# ir_array.net
KiCad netlist of a schematic drawn in EAGLE
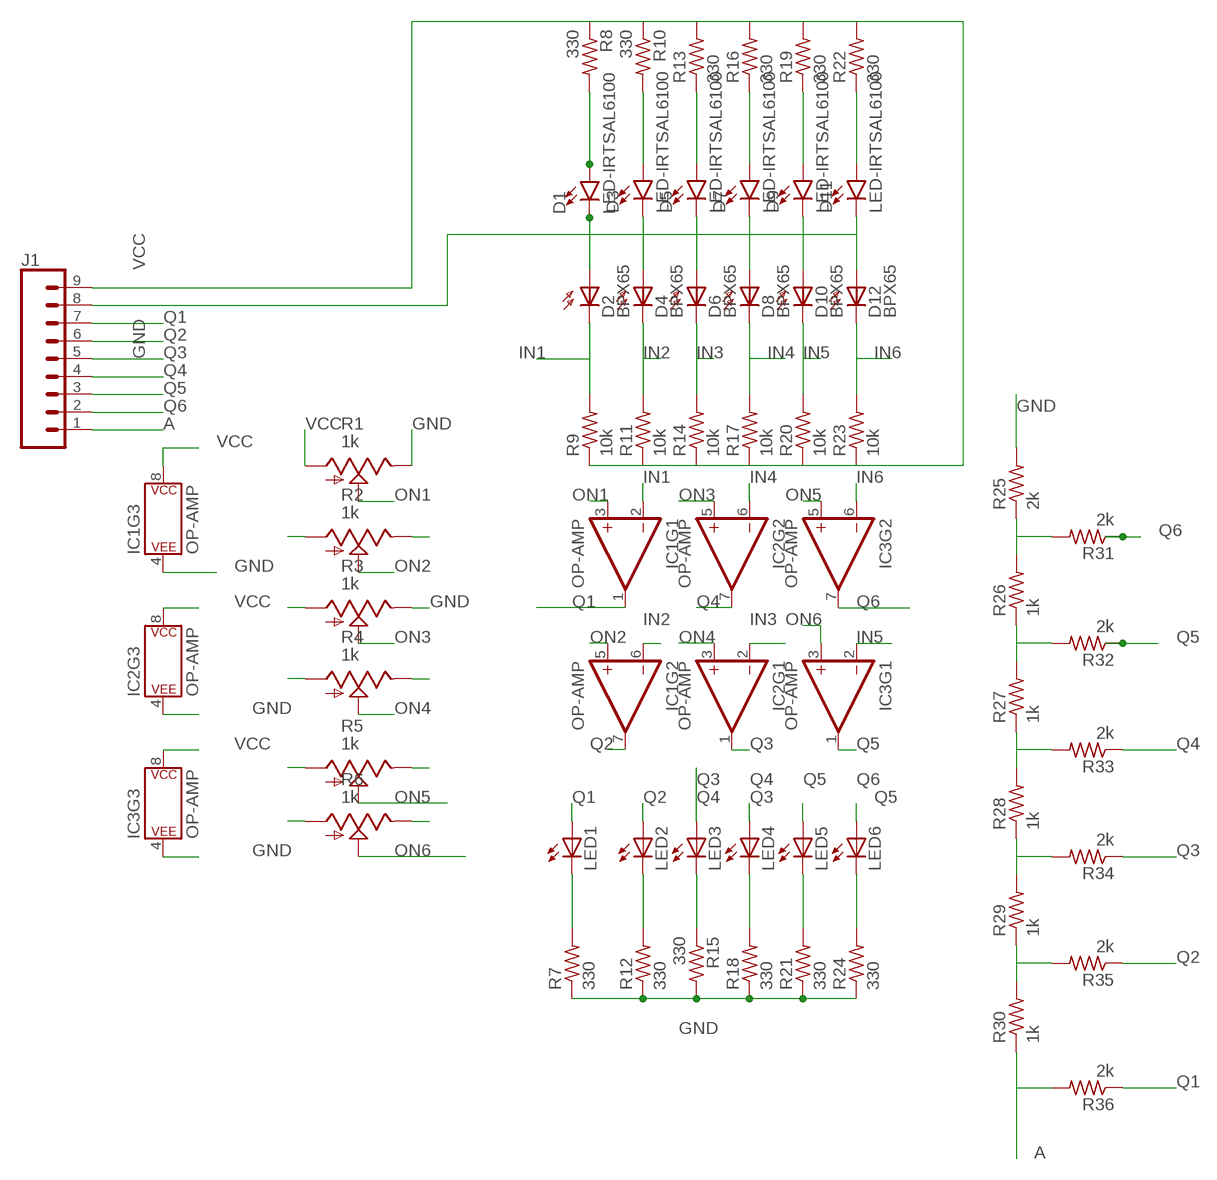
[diagram p0: schematic, sheet 1]

(export (version "E")
  (design (tool "Eeschema 10.0.6"))
  (components
    (comp (ref "D1")
      (value "LED-IRTSAL6100")
      (footprint "eagle-import:LED_5MM")
      (libsource (lib "eagle-import") (part "LED-IRTSAL6100"))
    )
    (comp (ref "D2")
      (value "BPX65")
      (footprint "eagle-import:BPX65")
      (fields (field (name "MPN") "BPX65."))
      (libsource (lib "eagle-import") (part "BPX65"))
    )
    (comp (ref "D3")
      (value "LED-IRTSAL6100")
      (footprint "eagle-import:LED_5MM")
      (libsource (lib "eagle-import") (part "LED-IRTSAL6100"))
    )
    (comp (ref "D4")
      (value "BPX65")
      (footprint "eagle-import:BPX65")
      (fields (field (name "MPN") "BPX65."))
      (libsource (lib "eagle-import") (part "BPX65"))
    )
    (comp (ref "D5")
      (value "LED-IRTSAL6100")
      (footprint "eagle-import:LED_5MM")
      (libsource (lib "eagle-import") (part "LED-IRTSAL6100"))
    )
    (comp (ref "D6")
      (value "BPX65")
      (footprint "eagle-import:BPX65")
      (fields (field (name "MPN") "BPX65."))
      (libsource (lib "eagle-import") (part "BPX65"))
    )
    (comp (ref "D7")
      (value "LED-IRTSAL6100")
      (footprint "eagle-import:LED_5MM")
      (libsource (lib "eagle-import") (part "LED-IRTSAL6100"))
    )
    (comp (ref "D8")
      (value "BPX65")
      (footprint "eagle-import:BPX65")
      (fields (field (name "MPN") "BPX65."))
      (libsource (lib "eagle-import") (part "BPX65"))
    )
    (comp (ref "D9")
      (value "LED-IRTSAL6100")
      (footprint "eagle-import:LED_5MM")
      (libsource (lib "eagle-import") (part "LED-IRTSAL6100"))
    )
    (comp (ref "D10")
      (value "BPX65")
      (footprint "eagle-import:BPX65")
      (fields (field (name "MPN") "BPX65."))
      (libsource (lib "eagle-import") (part "BPX65"))
    )
    (comp (ref "D11")
      (value "LED-IRTSAL6100")
      (footprint "eagle-import:LED_5MM")
      (libsource (lib "eagle-import") (part "LED-IRTSAL6100"))
    )
    (comp (ref "D12")
      (value "BPX65")
      (footprint "eagle-import:BPX65")
      (fields (field (name "MPN") "BPX65."))
      (libsource (lib "eagle-import") (part "BPX65"))
    )
    (comp (ref "IC1")
      (value "OP-AMP")
      (footprint "eagle-import:DIP08")
      (libsource (lib "eagle-import") (part "OPAMP-DUALDIP"))
    )
    (comp (ref "IC2")
      (value "OP-AMP")
      (footprint "eagle-import:DIP08")
      (libsource (lib "eagle-import") (part "OPAMP-DUALDIP"))
    )
    (comp (ref "IC3")
      (value "OP-AMP")
      (footprint "eagle-import:DIP08")
      (libsource (lib "eagle-import") (part "OPAMP-DUALDIP"))
    )
    (comp (ref "J1")
      (value "CONN_09")
      (footprint "eagle-import:1X09")
      (libsource (lib "eagle-import") (part "CONN_09"))
    )
    (comp (ref "LED1")
      (value "LED3MM")
      (footprint "eagle-import:LED3MM")
      (libsource (lib "eagle-import") (part "LED3MM"))
    )
    (comp (ref "LED2")
      (value "LED3MM")
      (footprint "eagle-import:LED3MM")
      (libsource (lib "eagle-import") (part "LED3MM"))
    )
    (comp (ref "LED3")
      (value "LED3MM")
      (footprint "eagle-import:LED3MM")
      (libsource (lib "eagle-import") (part "LED3MM"))
    )
    (comp (ref "LED4")
      (value "LED3MM")
      (footprint "eagle-import:LED3MM")
      (libsource (lib "eagle-import") (part "LED3MM"))
    )
    (comp (ref "LED5")
      (value "LED3MM")
      (footprint "eagle-import:LED3MM")
      (libsource (lib "eagle-import") (part "LED3MM"))
    )
    (comp (ref "LED6")
      (value "LED3MM")
      (footprint "eagle-import:LED3MM")
      (libsource (lib "eagle-import") (part "LED3MM"))
    )
    (comp (ref "R1")
      (value "1k")
      (footprint "eagle-import:B25P")
      (libsource (lib "eagle-import") (part "TRIM_US-B25P"))
    )
    (comp (ref "R2")
      (value "1k")
      (footprint "eagle-import:B25P")
      (libsource (lib "eagle-import") (part "TRIM_US-B25P"))
    )
    (comp (ref "R3")
      (value "1k")
      (footprint "eagle-import:B25P")
      (libsource (lib "eagle-import") (part "TRIM_US-B25P"))
    )
    (comp (ref "R4")
      (value "1k")
      (footprint "eagle-import:B25P")
      (libsource (lib "eagle-import") (part "TRIM_US-B25P"))
    )
    (comp (ref "R5")
      (value "1k")
      (footprint "eagle-import:B25P")
      (libsource (lib "eagle-import") (part "TRIM_US-B25P"))
    )
    (comp (ref "R6")
      (value "1k")
      (footprint "eagle-import:B25P")
      (libsource (lib "eagle-import") (part "TRIM_US-B25P"))
    )
    (comp (ref "R7")
      (value "330")
      (footprint "eagle-import:0207_9")
      (libsource (lib "eagle-import") (part "R-US_0207/9"))
    )
    (comp (ref "R8")
      (value "330")
      (footprint "eagle-import:0207_9")
      (libsource (lib "eagle-import") (part "R-US_0207/9"))
    )
    (comp (ref "R9")
      (value "10k")
      (footprint "eagle-import:0207_9")
      (libsource (lib "eagle-import") (part "R-US_0207/9"))
    )
    (comp (ref "R10")
      (value "330")
      (footprint "eagle-import:0207_9")
      (libsource (lib "eagle-import") (part "R-US_0207/9"))
    )
    (comp (ref "R11")
      (value "10k")
      (footprint "eagle-import:0207_9")
      (libsource (lib "eagle-import") (part "R-US_0207/9"))
    )
    (comp (ref "R12")
      (value "330")
      (footprint "eagle-import:0207_9")
      (libsource (lib "eagle-import") (part "R-US_0207/9"))
    )
    (comp (ref "R13")
      (value "330")
      (footprint "eagle-import:0207_9")
      (libsource (lib "eagle-import") (part "R-US_0207/9"))
    )
    (comp (ref "R14")
      (value "10k")
      (footprint "eagle-import:0207_9")
      (libsource (lib "eagle-import") (part "R-US_0207/9"))
    )
    (comp (ref "R15")
      (value "330")
      (footprint "eagle-import:0207_9")
      (libsource (lib "eagle-import") (part "R-US_0207/9"))
    )
    (comp (ref "R16")
      (value "330")
      (footprint "eagle-import:0207_9")
      (libsource (lib "eagle-import") (part "R-US_0207/9"))
    )
    (comp (ref "R17")
      (value "10k")
      (footprint "eagle-import:0207_9")
      (libsource (lib "eagle-import") (part "R-US_0207/9"))
    )
    (comp (ref "R18")
      (value "330")
      (footprint "eagle-import:0207_9")
      (libsource (lib "eagle-import") (part "R-US_0207/9"))
    )
    (comp (ref "R19")
      (value "330")
      (footprint "eagle-import:0207_9")
      (libsource (lib "eagle-import") (part "R-US_0207/9"))
    )
    (comp (ref "R20")
      (value "10k")
      (footprint "eagle-import:0207_9")
      (libsource (lib "eagle-import") (part "R-US_0207/9"))
    )
    (comp (ref "R21")
      (value "330")
      (footprint "eagle-import:0207_9")
      (libsource (lib "eagle-import") (part "R-US_0207/9"))
    )
    (comp (ref "R22")
      (value "330")
      (footprint "eagle-import:0207_9")
      (libsource (lib "eagle-import") (part "R-US_0207/9"))
    )
    (comp (ref "R23")
      (value "10k")
      (footprint "eagle-import:0207_9")
      (libsource (lib "eagle-import") (part "R-US_0207/9"))
    )
    (comp (ref "R24")
      (value "330")
      (footprint "eagle-import:0207_9")
      (libsource (lib "eagle-import") (part "R-US_0207/9"))
    )
    (comp (ref "R25")
      (value "2k")
      (footprint "eagle-import:0207_9")
      (libsource (lib "eagle-import") (part "R-US_0207/9"))
    )
    (comp (ref "R26")
      (value "1k")
      (footprint "eagle-import:0207_9")
      (libsource (lib "eagle-import") (part "R-US_0207/9"))
    )
    (comp (ref "R27")
      (value "1k")
      (footprint "eagle-import:0207_9")
      (libsource (lib "eagle-import") (part "R-US_0207/9"))
    )
    (comp (ref "R28")
      (value "1k")
      (footprint "eagle-import:0207_9")
      (libsource (lib "eagle-import") (part "R-US_0207/9"))
    )
    (comp (ref "R29")
      (value "1k")
      (footprint "eagle-import:0207_9")
      (libsource (lib "eagle-import") (part "R-US_0207/9"))
    )
    (comp (ref "R30")
      (value "1k")
      (footprint "eagle-import:0207_9")
      (libsource (lib "eagle-import") (part "R-US_0207/9"))
    )
    (comp (ref "R31")
      (value "2k")
      (footprint "eagle-import:0207_9")
      (libsource (lib "eagle-import") (part "R-US_0207/9"))
    )
    (comp (ref "R32")
      (value "2k")
      (footprint "eagle-import:0207_9")
      (libsource (lib "eagle-import") (part "R-US_0207/9"))
    )
    (comp (ref "R33")
      (value "2k")
      (footprint "eagle-import:0207_9")
      (libsource (lib "eagle-import") (part "R-US_0207/9"))
    )
    (comp (ref "R34")
      (value "2k")
      (footprint "eagle-import:0207_9")
      (libsource (lib "eagle-import") (part "R-US_0207/9"))
    )
    (comp (ref "R35")
      (value "2k")
      (footprint "eagle-import:0207_9")
      (libsource (lib "eagle-import") (part "R-US_0207/9"))
    )
    (comp (ref "R36")
      (value "2k")
      (footprint "eagle-import:0207_9")
      (libsource (lib "eagle-import") (part "R-US_0207/9"))
    )
  )
  (nets
    (net (code "1") (name "/A") (class "Default")
      (node (ref "J1") (pin "1") (pinfunction "1_1") (pintype "passive"))
      (node (ref "R30") (pin "1") (pinfunction "1_1") (pintype "passive"))
      (node (ref "R36") (pin "2") (pinfunction "2_2") (pintype "passive"))
    )
    (net (code "2") (name "/GND") (class "Default")
      (node (ref "D1") (pin "K") (pinfunction "C_K") (pintype "passive"))
      (node (ref "D10") (pin "A") (pinfunction "A_A") (pintype "passive"))
      (node (ref "D11") (pin "K") (pinfunction "C_K") (pintype "passive"))
      (node (ref "D12") (pin "A") (pinfunction "A_A") (pintype "passive"))
      (node (ref "D2") (pin "A") (pinfunction "A_A") (pintype "passive"))
      (node (ref "D3") (pin "K") (pinfunction "C_K") (pintype "passive"))
      (node (ref "D4") (pin "A") (pinfunction "A_A") (pintype "passive"))
      (node (ref "D5") (pin "K") (pinfunction "C_K") (pintype "passive"))
      (node (ref "D6") (pin "A") (pinfunction "A_A") (pintype "passive"))
      (node (ref "D7") (pin "K") (pinfunction "C_K") (pintype "passive"))
      (node (ref "D8") (pin "A") (pinfunction "A_A") (pintype "passive"))
      (node (ref "D9") (pin "K") (pinfunction "C_K") (pintype "passive"))
      (node (ref "IC1") (pin "4") (pinfunction "P$V-_4") (pintype "bidirectional"))
      (node (ref "IC2") (pin "4") (pinfunction "P$V-_4") (pintype "bidirectional"))
      (node (ref "IC3") (pin "4") (pinfunction "P$V-_4") (pintype "bidirectional"))
      (node (ref "J1") (pin "8") (pinfunction "8_8") (pintype "passive"))
      (node (ref "R1") (pin "E") (pinfunction "E_E") (pintype "passive"))
      (node (ref "R12") (pin "1") (pinfunction "1_1") (pintype "passive"))
      (node (ref "R15") (pin "2") (pinfunction "2_2") (pintype "passive"))
      (node (ref "R18") (pin "1") (pinfunction "1_1") (pintype "passive"))
      (node (ref "R2") (pin "E") (pinfunction "E_E") (pintype "passive"))
      (node (ref "R21") (pin "1") (pinfunction "1_1") (pintype "passive"))
      (node (ref "R24") (pin "1") (pinfunction "1_1") (pintype "passive"))
      (node (ref "R25") (pin "2") (pinfunction "2_2") (pintype "passive"))
      (node (ref "R3") (pin "E") (pinfunction "E_E") (pintype "passive"))
      (node (ref "R4") (pin "E") (pinfunction "E_E") (pintype "passive"))
      (node (ref "R5") (pin "E") (pinfunction "E_E") (pintype "passive"))
      (node (ref "R6") (pin "E") (pinfunction "E_E") (pintype "passive"))
      (node (ref "R7") (pin "1") (pinfunction "1_1") (pintype "passive"))
    )
    (net (code "3") (name "/IN1") (class "Default")
      (node (ref "D2") (pin "K") (pinfunction "C_K") (pintype "passive"))
      (node (ref "IC1") (pin "2") (pinfunction "-IN_2") (pintype "input"))
      (node (ref "R9") (pin "2") (pinfunction "2_2") (pintype "passive"))
    )
    (net (code "4") (name "/IN2") (class "Default")
      (node (ref "D4") (pin "K") (pinfunction "C_K") (pintype "passive"))
      (node (ref "IC1") (pin "6") (pinfunction "-IN_6") (pintype "input"))
      (node (ref "R11") (pin "2") (pinfunction "2_2") (pintype "passive"))
    )
    (net (code "5") (name "/IN3") (class "Default")
      (node (ref "D6") (pin "K") (pinfunction "C_K") (pintype "passive"))
      (node (ref "IC2") (pin "2") (pinfunction "-IN_2") (pintype "input"))
      (node (ref "R14") (pin "2") (pinfunction "2_2") (pintype "passive"))
    )
    (net (code "6") (name "/IN4") (class "Default")
      (node (ref "D8") (pin "K") (pinfunction "C_K") (pintype "passive"))
      (node (ref "IC2") (pin "6") (pinfunction "-IN_6") (pintype "input"))
      (node (ref "R17") (pin "2") (pinfunction "2_2") (pintype "passive"))
    )
    (net (code "7") (name "/IN5") (class "Default")
      (node (ref "D10") (pin "K") (pinfunction "C_K") (pintype "passive"))
      (node (ref "IC3") (pin "2") (pinfunction "-IN_2") (pintype "input"))
      (node (ref "R20") (pin "2") (pinfunction "2_2") (pintype "passive"))
    )
    (net (code "8") (name "/IN6") (class "Default")
      (node (ref "D12") (pin "K") (pinfunction "C_K") (pintype "passive"))
      (node (ref "IC3") (pin "6") (pinfunction "-IN_6") (pintype "input"))
      (node (ref "R23") (pin "2") (pinfunction "2_2") (pintype "passive"))
    )
    (net (code "9") (name "/ON1") (class "Default")
      (node (ref "IC1") (pin "3") (pinfunction "+IN_3") (pintype "input"))
      (node (ref "R1") (pin "S") (pinfunction "S_S") (pintype "passive"))
    )
    (net (code "10") (name "/ON2") (class "Default")
      (node (ref "IC1") (pin "5") (pinfunction "+IN_5") (pintype "input"))
      (node (ref "R2") (pin "S") (pinfunction "S_S") (pintype "passive"))
    )
    (net (code "11") (name "/ON3") (class "Default")
      (node (ref "IC2") (pin "5") (pinfunction "+IN_5") (pintype "input"))
      (node (ref "R3") (pin "S") (pinfunction "S_S") (pintype "passive"))
    )
    (net (code "12") (name "/ON4") (class "Default")
      (node (ref "IC2") (pin "3") (pinfunction "+IN_3") (pintype "input"))
      (node (ref "R4") (pin "S") (pinfunction "S_S") (pintype "passive"))
    )
    (net (code "13") (name "/ON5") (class "Default")
      (node (ref "IC3") (pin "5") (pinfunction "+IN_5") (pintype "input"))
      (node (ref "R5") (pin "S") (pinfunction "S_S") (pintype "passive"))
    )
    (net (code "14") (name "/ON6") (class "Default")
      (node (ref "IC3") (pin "3") (pinfunction "+IN_3") (pintype "input"))
      (node (ref "R6") (pin "S") (pinfunction "S_S") (pintype "passive"))
    )
    (net (code "15") (name "/Q1") (class "Default")
      (node (ref "IC1") (pin "1") (pinfunction "OUT_1") (pintype "output"))
      (node (ref "J1") (pin "7") (pinfunction "7_7") (pintype "passive"))
      (node (ref "LED1") (pin "A") (pinfunction "A_A") (pintype "passive"))
      (node (ref "R36") (pin "1") (pinfunction "1_1") (pintype "passive"))
    )
    (net (code "16") (name "/Q2") (class "Default")
      (node (ref "IC1") (pin "7") (pinfunction "OUT_7") (pintype "output"))
      (node (ref "J1") (pin "6") (pinfunction "6_6") (pintype "passive"))
      (node (ref "LED2") (pin "A") (pinfunction "A_A") (pintype "passive"))
      (node (ref "R35") (pin "1") (pinfunction "1_1") (pintype "passive"))
    )
    (net (code "17") (name "/Q3") (class "Default")
      (node (ref "IC2") (pin "1") (pinfunction "OUT_1") (pintype "output"))
      (node (ref "J1") (pin "5") (pinfunction "5_5") (pintype "passive"))
      (node (ref "LED3") (pin "A") (pinfunction "A_A") (pintype "passive"))
      (node (ref "R34") (pin "1") (pinfunction "1_1") (pintype "passive"))
    )
    (net (code "18") (name "/Q4") (class "Default")
      (node (ref "IC2") (pin "7") (pinfunction "OUT_7") (pintype "output"))
      (node (ref "J1") (pin "4") (pinfunction "4_4") (pintype "passive"))
      (node (ref "LED4") (pin "A") (pinfunction "A_A") (pintype "passive"))
      (node (ref "R33") (pin "1") (pinfunction "1_1") (pintype "passive"))
    )
    (net (code "19") (name "/Q5") (class "Default")
      (node (ref "IC3") (pin "1") (pinfunction "OUT_1") (pintype "output"))
      (node (ref "J1") (pin "3") (pinfunction "3_3") (pintype "passive"))
      (node (ref "LED5") (pin "A") (pinfunction "A_A") (pintype "passive"))
      (node (ref "R32") (pin "1") (pinfunction "1_1") (pintype "passive"))
    )
    (net (code "20") (name "/Q6") (class "Default")
      (node (ref "IC3") (pin "7") (pinfunction "OUT_7") (pintype "output"))
      (node (ref "J1") (pin "2") (pinfunction "2_2") (pintype "passive"))
      (node (ref "LED6") (pin "A") (pinfunction "A_A") (pintype "passive"))
      (node (ref "R31") (pin "1") (pinfunction "1_1") (pintype "passive"))
    )
    (net (code "21") (name "/VCC") (class "Default")
      (node (ref "IC1") (pin "8") (pinfunction "P$V+_8") (pintype "bidirectional"))
      (node (ref "IC2") (pin "8") (pinfunction "P$V+_8") (pintype "bidirectional"))
      (node (ref "IC3") (pin "8") (pinfunction "P$V+_8") (pintype "bidirectional"))
      (node (ref "J1") (pin "9") (pinfunction "9_9") (pintype "passive"))
      (node (ref "R1") (pin "A") (pinfunction "A_A") (pintype "passive"))
      (node (ref "R10") (pin "1") (pinfunction "1_1") (pintype "passive"))
      (node (ref "R11") (pin "1") (pinfunction "1_1") (pintype "passive"))
      (node (ref "R13") (pin "2") (pinfunction "2_2") (pintype "passive"))
      (node (ref "R14") (pin "1") (pinfunction "1_1") (pintype "passive"))
      (node (ref "R16") (pin "2") (pinfunction "2_2") (pintype "passive"))
      (node (ref "R17") (pin "1") (pinfunction "1_1") (pintype "passive"))
      (node (ref "R19") (pin "2") (pinfunction "2_2") (pintype "passive"))
      (node (ref "R2") (pin "A") (pinfunction "A_A") (pintype "passive"))
      (node (ref "R20") (pin "1") (pinfunction "1_1") (pintype "passive"))
      (node (ref "R22") (pin "2") (pinfunction "2_2") (pintype "passive"))
      (node (ref "R23") (pin "1") (pinfunction "1_1") (pintype "passive"))
      (node (ref "R3") (pin "A") (pinfunction "A_A") (pintype "passive"))
      (node (ref "R4") (pin "A") (pinfunction "A_A") (pintype "passive"))
      (node (ref "R5") (pin "A") (pinfunction "A_A") (pintype "passive"))
      (node (ref "R6") (pin "A") (pinfunction "A_A") (pintype "passive"))
      (node (ref "R8") (pin "1") (pinfunction "1_1") (pintype "passive"))
      (node (ref "R9") (pin "1") (pinfunction "1_1") (pintype "passive"))
    )
    (net (code "22") (name "Net-(D1-PadA)") (class "Default")
      (node (ref "D1") (pin "A") (pinfunction "A_A") (pintype "passive"))
      (node (ref "R8") (pin "2") (pinfunction "2_2") (pintype "passive"))
    )
    (net (code "23") (name "Net-(D3-PadA)") (class "Default")
      (node (ref "D3") (pin "A") (pinfunction "A_A") (pintype "passive"))
      (node (ref "R10") (pin "2") (pinfunction "2_2") (pintype "passive"))
    )
    (net (code "24") (name "Net-(D5-PadA)") (class "Default")
      (node (ref "D5") (pin "A") (pinfunction "A_A") (pintype "passive"))
      (node (ref "R13") (pin "1") (pinfunction "1_1") (pintype "passive"))
    )
    (net (code "25") (name "Net-(D7-PadA)") (class "Default")
      (node (ref "D7") (pin "A") (pinfunction "A_A") (pintype "passive"))
      (node (ref "R16") (pin "1") (pinfunction "1_1") (pintype "passive"))
    )
    (net (code "26") (name "Net-(D9-PadA)") (class "Default")
      (node (ref "D9") (pin "A") (pinfunction "A_A") (pintype "passive"))
      (node (ref "R19") (pin "1") (pinfunction "1_1") (pintype "passive"))
    )
    (net (code "27") (name "Net-(D11-PadA)") (class "Default")
      (node (ref "D11") (pin "A") (pinfunction "A_A") (pintype "passive"))
      (node (ref "R22") (pin "1") (pinfunction "1_1") (pintype "passive"))
    )
    (net (code "28") (name "Net-(LED1-C)") (class "Default")
      (node (ref "LED1") (pin "K") (pinfunction "C_K") (pintype "passive"))
      (node (ref "R7") (pin "2") (pinfunction "2_2") (pintype "passive"))
    )
    (net (code "29") (name "Net-(LED2-C)") (class "Default")
      (node (ref "LED2") (pin "K") (pinfunction "C_K") (pintype "passive"))
      (node (ref "R12") (pin "2") (pinfunction "2_2") (pintype "passive"))
    )
    (net (code "30") (name "Net-(LED3-C)") (class "Default")
      (node (ref "LED3") (pin "K") (pinfunction "C_K") (pintype "passive"))
      (node (ref "R15") (pin "1") (pinfunction "1_1") (pintype "passive"))
    )
    (net (code "31") (name "Net-(LED4-C)") (class "Default")
      (node (ref "LED4") (pin "K") (pinfunction "C_K") (pintype "passive"))
      (node (ref "R18") (pin "2") (pinfunction "2_2") (pintype "passive"))
    )
    (net (code "32") (name "Net-(LED5-C)") (class "Default")
      (node (ref "LED5") (pin "K") (pinfunction "C_K") (pintype "passive"))
      (node (ref "R21") (pin "2") (pinfunction "2_2") (pintype "passive"))
    )
    (net (code "33") (name "Net-(LED6-C)") (class "Default")
      (node (ref "LED6") (pin "K") (pinfunction "C_K") (pintype "passive"))
      (node (ref "R24") (pin "2") (pinfunction "2_2") (pintype "passive"))
    )
    (net (code "34") (name "Net-(R25-Pad1)") (class "Default")
      (node (ref "R25") (pin "1") (pinfunction "1_1") (pintype "passive"))
      (node (ref "R26") (pin "2") (pinfunction "2_2") (pintype "passive"))
      (node (ref "R31") (pin "2") (pinfunction "2_2") (pintype "passive"))
    )
    (net (code "35") (name "Net-(R26-Pad1)") (class "Default")
      (node (ref "R26") (pin "1") (pinfunction "1_1") (pintype "passive"))
      (node (ref "R27") (pin "2") (pinfunction "2_2") (pintype "passive"))
      (node (ref "R32") (pin "2") (pinfunction "2_2") (pintype "passive"))
    )
    (net (code "36") (name "Net-(R27-Pad1)") (class "Default")
      (node (ref "R27") (pin "1") (pinfunction "1_1") (pintype "passive"))
      (node (ref "R28") (pin "2") (pinfunction "2_2") (pintype "passive"))
      (node (ref "R33") (pin "2") (pinfunction "2_2") (pintype "passive"))
    )
    (net (code "37") (name "Net-(R28-Pad1)") (class "Default")
      (node (ref "R28") (pin "1") (pinfunction "1_1") (pintype "passive"))
      (node (ref "R29") (pin "2") (pinfunction "2_2") (pintype "passive"))
      (node (ref "R34") (pin "2") (pinfunction "2_2") (pintype "passive"))
    )
    (net (code "38") (name "Net-(R29-Pad1)") (class "Default")
      (node (ref "R29") (pin "1") (pinfunction "1_1") (pintype "passive"))
      (node (ref "R30") (pin "2") (pinfunction "2_2") (pintype "passive"))
      (node (ref "R35") (pin "2") (pinfunction "2_2") (pintype "passive"))
    )
  )
)
